# PLCBOARD.net
KiCad netlist of a schematic drawn in Altium Designer
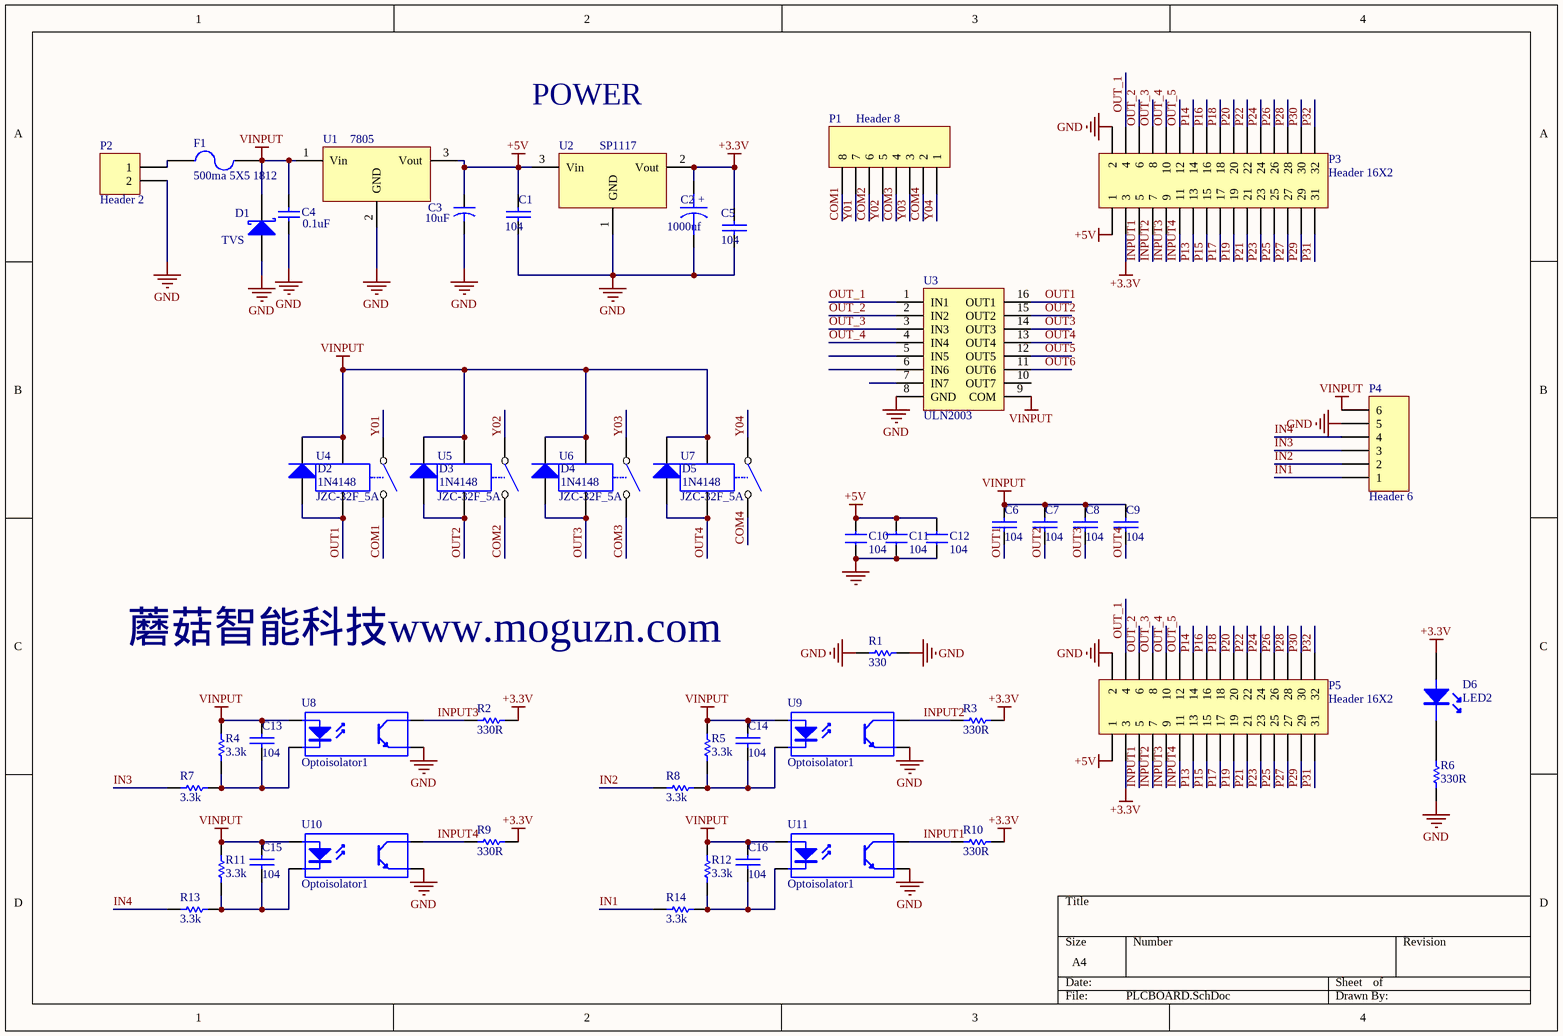
[diagram p0: PLCBOARD.SchDoc]

(export (version "E")
  (design (tool "Eeschema 10.0.6"))
  (components
    (comp (ref "C1")
      (value "104")
      (footprint "0805C1")
      (description "Capacitor")
      (libsource (lib "*") (part "CAP"))
    )
    (comp (ref "C2")
      (value "1000uf")
      (footprint "c6.3*5.3")
      (description "Capacitor")
      (libsource (lib "*") (part "CAPACITOR POL"))
    )
    (comp (ref "C3")
      (value "10uF")
      (footprint "RB.2/.4")
      (description "Capacitor")
      (fields (field (name "Comment") "Cap2") (field (name "PUBLISHER") "Altium Limited"))
      (libsource (lib "Miscellaneous Devices") (part "Cap2"))
    )
    (comp (ref "C4")
      (value "0.1uF")
      (footprint "0805C1")
      (description "Capacitor")
      (fields (field (name "Comment") "Cap") (field (name "PUBLISHER") "Altium Limited"))
      (libsource (lib "Miscellaneous Devices") (part "Cap"))
    )
    (comp (ref "C5")
      (value "104")
      (footprint "0805C1")
      (description "Capacitor")
      (libsource (lib "*") (part "CAP"))
    )
    (comp (ref "C6")
      (value "104")
      (footprint "0805C1")
      (description "Capacitor")
      (libsource (lib "*") (part "CAP"))
    )
    (comp (ref "C7")
      (value "104")
      (footprint "0805C1")
      (description "Capacitor")
      (libsource (lib "*") (part "CAP"))
    )
    (comp (ref "C8")
      (value "104")
      (footprint "0805C1")
      (description "Capacitor")
      (libsource (lib "*") (part "CAP"))
    )
    (comp (ref "C9")
      (value "104")
      (footprint "0805C1")
      (description "Capacitor")
      (libsource (lib "*") (part "CAP"))
    )
    (comp (ref "C10")
      (value "104")
      (footprint "0805C1")
      (description "Capacitor")
      (libsource (lib "") (part "CAP_1"))
    )
    (comp (ref "C11")
      (value "104")
      (footprint "0805C1")
      (description "Capacitor")
      (libsource (lib "") (part "CAP_1"))
    )
    (comp (ref "C12")
      (value "104")
      (footprint "0805C1")
      (description "Capacitor")
      (libsource (lib "") (part "CAP_1"))
    )
    (comp (ref "C13")
      (value "104")
      (footprint "0805C1")
      (description "Capacitor")
      (libsource (lib "*") (part "CAP"))
    )
    (comp (ref "C14")
      (value "104")
      (footprint "0805C1")
      (description "Capacitor")
      (libsource (lib "*") (part "CAP"))
    )
    (comp (ref "C15")
      (value "104")
      (footprint "0805C1")
      (description "Capacitor")
      (libsource (lib "*") (part "CAP"))
    )
    (comp (ref "C16")
      (value "104")
      (footprint "0805C1")
      (description "Capacitor")
      (libsource (lib "*") (part "CAP"))
    )
    (comp (ref "D1")
      (value "TVS")
      (footprint "do-214")
      (description "Schottky Diode")
      (fields (field (name "PUBLISHER") "Altium Limited"))
      (libsource (lib "Miscellaneous Devices") (part "D Schottky"))
    )
    (comp (ref "D2")
      (value "1N4148")
      (footprint "DIODE_SMD_4148")
      (description "Default Diode")
      (fields (field (name "PUBLISHER") "Altium Limited"))
      (libsource (lib "Miscellaneous Devices") (part "Diode"))
    )
    (comp (ref "D3")
      (value "1N4148")
      (footprint "DIODE_SMD_4148")
      (description "Default Diode")
      (fields (field (name "PUBLISHER") "Altium Limited"))
      (libsource (lib "Miscellaneous Devices") (part "Diode"))
    )
    (comp (ref "D4")
      (value "1N4148")
      (footprint "DIODE_SMD_4148")
      (description "Default Diode")
      (fields (field (name "PUBLISHER") "Altium Limited"))
      (libsource (lib "Miscellaneous Devices") (part "Diode"))
    )
    (comp (ref "D5")
      (value "1N4148")
      (footprint "DIODE_SMD_4148")
      (description "Default Diode")
      (fields (field (name "PUBLISHER") "Altium Limited"))
      (libsource (lib "Miscellaneous Devices") (part "Diode"))
    )
    (comp (ref "D6") (value "LED2") (footprint "0805LED") (libsource (lib "*") (part "LED")))
    (comp (ref "F1")
      (value "500ma 5X5 1812")
      (footprint "1812R")
      (description "Fuse")
      (fields (field (name "PUBLISHER") "Altium Limited"))
      (libsource (lib "Miscellaneous Devices") (part "Fuse 2"))
    )
    (comp (ref "P1")
      (value "Header 8")
      (footprint "CON8.6_8pin")
      (description "Header, 8-Pin")
      (fields (field (name "PUBLISHER") "Altium Limited"))
      (libsource (lib "Miscellaneous Connectors") (part "Header 8"))
    )
    (comp (ref "P2")
      (value "Header 2")
      (footprint "5VINPUT")
      (description "Header, 2-Pin")
      (fields (field (name "PUBLISHER") "Altium Limited"))
      (libsource (lib "Miscellaneous Connectors") (part "Header 2"))
    )
    (comp (ref "P3")
      (value "Header 16X2")
      (footprint "NDK2X16")
      (description "Header, 16-Pin, Dual row")
      (fields (field (name "PUBLISHER") "Altium Limited"))
      (libsource (lib "Miscellaneous Connectors") (part "Header 16X2"))
    )
    (comp (ref "P4")
      (value "Header 6")
      (footprint "CON7.62_6pin")
      (description "Header, 6-Pin")
      (fields (field (name "PUBLISHER") "Altium Limited"))
      (libsource (lib "Miscellaneous Connectors") (part "Header 6"))
    )
    (comp (ref "P5")
      (value "Header 16X2")
      (footprint "HDR2X16")
      (description "Header, 16-Pin, Dual row")
      (fields (field (name "PUBLISHER") "Altium Limited"))
      (libsource (lib "Miscellaneous Connectors") (part "Header 16X2"))
    )
    (comp (ref "R1")
      (value "330")
      (footprint "1812R")
      (description "Resistor")
      (fields (field (name "Comment") "Res1") (field (name "PUBLISHER") "Altium Limited"))
      (libsource (lib "Miscellaneous Devices") (part "Res1"))
    )
    (comp (ref "R2")
      (value "330R")
      (footprint "0805R1")
      (description "Resistor")
      (fields (field (name "Comment") "Res1") (field (name "PUBLISHER") "Altium Limited"))
      (libsource (lib "Miscellaneous Devices") (part "Res1"))
    )
    (comp (ref "R3")
      (value "330R")
      (footprint "0805R1")
      (description "Resistor")
      (fields (field (name "Comment") "Res1") (field (name "PUBLISHER") "Altium Limited"))
      (libsource (lib "Miscellaneous Devices") (part "Res1"))
    )
    (comp (ref "R4")
      (value "3.3k")
      (footprint "0805R1")
      (description "Resistor")
      (fields (field (name "Comment") "Res1") (field (name "PUBLISHER") "Altium Limited"))
      (libsource (lib "Miscellaneous Devices") (part "Res1"))
    )
    (comp (ref "R5")
      (value "3.3k")
      (footprint "0805R1")
      (description "Resistor")
      (fields (field (name "Comment") "Res1") (field (name "PUBLISHER") "Altium Limited"))
      (libsource (lib "Miscellaneous Devices") (part "Res1"))
    )
    (comp (ref "R6")
      (value "330R")
      (footprint "0805R1")
      (description "Resistor")
      (fields (field (name "Comment") "Res1") (field (name "PUBLISHER") "Altium Limited"))
      (libsource (lib "Miscellaneous Devices") (part "Res1"))
    )
    (comp (ref "R7")
      (value "3.3k")
      (footprint "0805R1")
      (description "Resistor")
      (fields (field (name "Comment") "Res1") (field (name "PUBLISHER") "Altium Limited"))
      (libsource (lib "Miscellaneous Devices") (part "Res1"))
    )
    (comp (ref "R8")
      (value "3.3k")
      (footprint "0805R1")
      (description "Resistor")
      (fields (field (name "Comment") "Res1") (field (name "PUBLISHER") "Altium Limited"))
      (libsource (lib "Miscellaneous Devices") (part "Res1"))
    )
    (comp (ref "R9")
      (value "330R")
      (footprint "0805R1")
      (description "Resistor")
      (fields (field (name "Comment") "Res1") (field (name "PUBLISHER") "Altium Limited"))
      (libsource (lib "Miscellaneous Devices") (part "Res1"))
    )
    (comp (ref "R10")
      (value "330R")
      (footprint "0805R1")
      (description "Resistor")
      (fields (field (name "Comment") "Res1") (field (name "PUBLISHER") "Altium Limited"))
      (libsource (lib "Miscellaneous Devices") (part "Res1"))
    )
    (comp (ref "R11")
      (value "3.3k")
      (footprint "0805R1")
      (description "Resistor")
      (fields (field (name "Comment") "Res1") (field (name "PUBLISHER") "Altium Limited"))
      (libsource (lib "Miscellaneous Devices") (part "Res1"))
    )
    (comp (ref "R12")
      (value "3.3k")
      (footprint "0805R1")
      (description "Resistor")
      (fields (field (name "Comment") "Res1") (field (name "PUBLISHER") "Altium Limited"))
      (libsource (lib "Miscellaneous Devices") (part "Res1"))
    )
    (comp (ref "R13")
      (value "3.3k")
      (footprint "0805R1")
      (description "Resistor")
      (fields (field (name "Comment") "Res1") (field (name "PUBLISHER") "Altium Limited"))
      (libsource (lib "Miscellaneous Devices") (part "Res1"))
    )
    (comp (ref "R14")
      (value "3.3k")
      (footprint "0805R1")
      (description "Resistor")
      (fields (field (name "Comment") "Res1") (field (name "PUBLISHER") "Altium Limited"))
      (libsource (lib "Miscellaneous Devices") (part "Res1"))
    )
    (comp (ref "U1") (value "7805") (footprint "7805") (libsource (lib "*") (part "7800")))
    (comp (ref "U2") (value "SP1117") (footprint "SOT-223") (libsource (lib "hhregulator") (part "SP1117")))
    (comp (ref "U3") (value "ULN2003") (footprint "SO-16") (libsource (lib "hhic") (part "ULN2003")))
    (comp (ref "U4")
      (value "JZC-32F_5A")
      (footprint "JZC-32F_5A")
      (libsource (lib "hhrelay") (part "JZC-32F_5A"))
    )
    (comp (ref "U5")
      (value "JZC-32F_5A")
      (footprint "JZC-32F_5A")
      (libsource (lib "hhrelay") (part "JZC-32F_5A"))
    )
    (comp (ref "U6")
      (value "JZC-32F_5A")
      (footprint "JZC-32F_5A")
      (libsource (lib "hhrelay") (part "JZC-32F_5A"))
    )
    (comp (ref "U7")
      (value "JZC-32F_5A")
      (footprint "NT90RHAE12CB_30A")
      (libsource (lib "hhrelay") (part "JZC-32F_5A"))
    )
    (comp (ref "U8")
      (value "Optoisolator1")
      (footprint "TLP181-2")
      (description "4-Pin Phototransistor Optocoupler")
      (fields (field (name "PUBLISHER") "Altium Limited"))
      (libsource (lib "Miscellaneous Devices") (part "Optoisolator1"))
    )
    (comp (ref "U9")
      (value "Optoisolator1")
      (footprint "TLP181-2")
      (description "4-Pin Phototransistor Optocoupler")
      (fields (field (name "PUBLISHER") "Altium Limited"))
      (libsource (lib "Miscellaneous Devices") (part "Optoisolator1"))
    )
    (comp (ref "U10")
      (value "Optoisolator1")
      (footprint "TLP181-2")
      (description "4-Pin Phototransistor Optocoupler")
      (fields (field (name "PUBLISHER") "Altium Limited"))
      (libsource (lib "Miscellaneous Devices") (part "Optoisolator1"))
    )
    (comp (ref "U11")
      (value "Optoisolator1")
      (footprint "TLP181-2")
      (description "4-Pin Phototransistor Optocoupler")
      (fields (field (name "PUBLISHER") "Altium Limited"))
      (libsource (lib "Miscellaneous Devices") (part "Optoisolator1"))
    )
  )
  (nets
    (net (code "1") (name "+3.3V") (class "Default")
      (node (ref "C2") (pin "1") (pinfunction "1_1") (pintype "passive"))
      (node (ref "C5") (pin "1") (pinfunction "1_1") (pintype "passive"))
      (node (ref "D6") (pin "1") (pinfunction "1_1") (pintype "passive"))
      (node (ref "P3") (pin "3") (pinfunction "3_3") (pintype "passive"))
      (node (ref "P5") (pin "3") (pinfunction "3_3") (pintype "passive"))
      (node (ref "R10") (pin "1") (pinfunction "1_1") (pintype "passive"))
      (node (ref "R2") (pin "1") (pinfunction "1_1") (pintype "passive"))
      (node (ref "R3") (pin "1") (pinfunction "1_1") (pintype "passive"))
      (node (ref "R9") (pin "1") (pinfunction "1_1") (pintype "passive"))
      (node (ref "U2") (pin "2") (pinfunction "Vout_2") (pintype "passive"))
    )
    (net (code "2") (name "+5V") (class "Default")
      (node (ref "C1") (pin "1") (pinfunction "1_1") (pintype "passive"))
      (node (ref "C10") (pin "2") (pinfunction "2_2") (pintype "passive"))
      (node (ref "C11") (pin "2") (pinfunction "2_2") (pintype "passive"))
      (node (ref "C12") (pin "2") (pinfunction "2_2") (pintype "passive"))
      (node (ref "C3") (pin "1") (pinfunction "1_1") (pintype "passive"))
      (node (ref "P3") (pin "1") (pinfunction "1_1") (pintype "passive"))
      (node (ref "P5") (pin "1") (pinfunction "1_1") (pintype "passive"))
      (node (ref "U1") (pin "3") (pinfunction "Vout_3") (pintype "passive"))
      (node (ref "U2") (pin "3") (pinfunction "Vin_3") (pintype "passive"))
    )
    (net (code "3") (name "/COM1") (class "Default")
      (node (ref "P1") (pin "8") (pinfunction "8_8") (pintype "passive"))
      (node (ref "U4") (pin "2") (pinfunction "2_2") (pintype "passive"))
    )
    (net (code "4") (name "/COM2") (class "Default")
      (node (ref "P1") (pin "6") (pinfunction "6_6") (pintype "passive"))
      (node (ref "U5") (pin "2") (pinfunction "2_2") (pintype "passive"))
    )
    (net (code "5") (name "/COM3") (class "Default")
      (node (ref "P1") (pin "4") (pinfunction "4_4") (pintype "passive"))
      (node (ref "U6") (pin "2") (pinfunction "2_2") (pintype "passive"))
    )
    (net (code "6") (name "/COM4") (class "Default")
      (node (ref "P1") (pin "2") (pinfunction "2_2") (pintype "passive"))
      (node (ref "U7") (pin "2") (pinfunction "2_2") (pintype "passive"))
    )
    (net (code "7") (name "/IN1") (class "Default")
      (node (ref "P4") (pin "1") (pinfunction "1_1") (pintype "passive"))
      (node (ref "R14") (pin "1") (pinfunction "1_1") (pintype "passive"))
    )
    (net (code "8") (name "/IN2") (class "Default")
      (node (ref "P4") (pin "2") (pinfunction "2_2") (pintype "passive"))
      (node (ref "R8") (pin "1") (pinfunction "1_1") (pintype "passive"))
    )
    (net (code "9") (name "/IN3") (class "Default")
      (node (ref "P4") (pin "3") (pinfunction "3_3") (pintype "passive"))
      (node (ref "R7") (pin "1") (pinfunction "1_1") (pintype "passive"))
    )
    (net (code "10") (name "/IN4") (class "Default")
      (node (ref "P4") (pin "4") (pinfunction "4_4") (pintype "passive"))
      (node (ref "R13") (pin "1") (pinfunction "1_1") (pintype "passive"))
    )
    (net (code "11") (name "/INPUT1") (class "Default")
      (node (ref "P3") (pin "5") (pinfunction "5_5") (pintype "passive"))
      (node (ref "P5") (pin "5") (pinfunction "5_5") (pintype "passive"))
      (node (ref "R10") (pin "2") (pinfunction "2_2") (pintype "passive"))
      (node (ref "U11") (pin "4") (pinfunction "C_4") (pintype "passive"))
    )
    (net (code "12") (name "/INPUT2") (class "Default")
      (node (ref "P3") (pin "7") (pinfunction "7_7") (pintype "passive"))
      (node (ref "P5") (pin "7") (pinfunction "7_7") (pintype "passive"))
      (node (ref "R3") (pin "2") (pinfunction "2_2") (pintype "passive"))
      (node (ref "U9") (pin "4") (pinfunction "C_4") (pintype "passive"))
    )
    (net (code "13") (name "/INPUT3") (class "Default")
      (node (ref "P3") (pin "9") (pinfunction "9_9") (pintype "passive"))
      (node (ref "P5") (pin "9") (pinfunction "9_9") (pintype "passive"))
      (node (ref "R2") (pin "2") (pinfunction "2_2") (pintype "passive"))
      (node (ref "U8") (pin "4") (pinfunction "C_4") (pintype "passive"))
    )
    (net (code "14") (name "/INPUT4") (class "Default")
      (node (ref "P3") (pin "11") (pinfunction "11_11") (pintype "passive"))
      (node (ref "P5") (pin "11") (pinfunction "11_11") (pintype "passive"))
      (node (ref "R9") (pin "2") (pinfunction "2_2") (pintype "passive"))
      (node (ref "U10") (pin "4") (pinfunction "C_4") (pintype "passive"))
    )
    (net (code "15") (name "/OUT1") (class "Default")
      (node (ref "C6") (pin "2") (pinfunction "2_2") (pintype "passive"))
      (node (ref "D2") (pin "1") (pinfunction "A_1") (pintype "passive"))
      (node (ref "U3") (pin "16") (pinfunction "OUT1_16") (pintype "passive"))
      (node (ref "U4") (pin "4") (pinfunction "4_4") (pintype "passive"))
    )
    (net (code "16") (name "/OUT2") (class "Default")
      (node (ref "C7") (pin "2") (pinfunction "2_2") (pintype "passive"))
      (node (ref "D3") (pin "1") (pinfunction "A_1") (pintype "passive"))
      (node (ref "U3") (pin "15") (pinfunction "OUT2_15") (pintype "passive"))
      (node (ref "U5") (pin "4") (pinfunction "4_4") (pintype "passive"))
    )
    (net (code "17") (name "/OUT3") (class "Default")
      (node (ref "C8") (pin "2") (pinfunction "2_2") (pintype "passive"))
      (node (ref "D4") (pin "1") (pinfunction "A_1") (pintype "passive"))
      (node (ref "U3") (pin "14") (pinfunction "OUT3_14") (pintype "passive"))
      (node (ref "U6") (pin "4") (pinfunction "4_4") (pintype "passive"))
    )
    (net (code "18") (name "/OUT4") (class "Default")
      (node (ref "C9") (pin "2") (pinfunction "2_2") (pintype "passive"))
      (node (ref "D5") (pin "1") (pinfunction "A_1") (pintype "passive"))
      (node (ref "U3") (pin "13") (pinfunction "OUT4_13") (pintype "passive"))
      (node (ref "U7") (pin "4") (pinfunction "4_4") (pintype "passive"))
    )
    (net (code "19") (name "/OUT5") (class "Default")
      (node (ref "U3") (pin "12") (pinfunction "OUT5_12") (pintype "passive"))
    )
    (net (code "20") (name "/OUT6") (class "Default")
      (node (ref "U3") (pin "11") (pinfunction "OUT6_11") (pintype "passive"))
    )
    (net (code "21") (name "/OUT_1") (class "Default")
      (node (ref "P3") (pin "4") (pinfunction "4_4") (pintype "passive"))
      (node (ref "P5") (pin "4") (pinfunction "4_4") (pintype "passive"))
      (node (ref "U3") (pin "1") (pinfunction "IN1_1") (pintype "passive"))
    )
    (net (code "22") (name "/OUT_2") (class "Default")
      (node (ref "P3") (pin "6") (pinfunction "6_6") (pintype "passive"))
      (node (ref "P5") (pin "6") (pinfunction "6_6") (pintype "passive"))
      (node (ref "U3") (pin "2") (pinfunction "IN2_2") (pintype "passive"))
    )
    (net (code "23") (name "/OUT_3") (class "Default")
      (node (ref "P3") (pin "8") (pinfunction "8_8") (pintype "passive"))
      (node (ref "P5") (pin "8") (pinfunction "8_8") (pintype "passive"))
      (node (ref "U3") (pin "3") (pinfunction "IN3_3") (pintype "passive"))
    )
    (net (code "24") (name "/OUT_4") (class "Default")
      (node (ref "P3") (pin "10") (pinfunction "10_10") (pintype "passive"))
      (node (ref "P5") (pin "10") (pinfunction "10_10") (pintype "passive"))
      (node (ref "U3") (pin "4") (pinfunction "IN4_4") (pintype "passive"))
    )
    (net (code "25") (name "/OUT_5") (class "Default")
      (node (ref "P3") (pin "12") (pinfunction "12_12") (pintype "passive"))
      (node (ref "P5") (pin "12") (pinfunction "12_12") (pintype "passive"))
    )
    (net (code "26") (name "/P13") (class "Default")
      (node (ref "P3") (pin "13") (pinfunction "13_13") (pintype "passive"))
      (node (ref "P5") (pin "13") (pinfunction "13_13") (pintype "passive"))
    )
    (net (code "27") (name "/P14") (class "Default")
      (node (ref "P3") (pin "14") (pinfunction "14_14") (pintype "passive"))
      (node (ref "P5") (pin "14") (pinfunction "14_14") (pintype "passive"))
    )
    (net (code "28") (name "/P15") (class "Default")
      (node (ref "P3") (pin "15") (pinfunction "15_15") (pintype "passive"))
      (node (ref "P5") (pin "15") (pinfunction "15_15") (pintype "passive"))
    )
    (net (code "29") (name "/P16") (class "Default")
      (node (ref "P3") (pin "16") (pinfunction "16_16") (pintype "passive"))
      (node (ref "P5") (pin "16") (pinfunction "16_16") (pintype "passive"))
    )
    (net (code "30") (name "/P17") (class "Default")
      (node (ref "P3") (pin "17") (pinfunction "17_17") (pintype "passive"))
      (node (ref "P5") (pin "17") (pinfunction "17_17") (pintype "passive"))
    )
    (net (code "31") (name "/P18") (class "Default")
      (node (ref "P3") (pin "18") (pinfunction "18_18") (pintype "passive"))
      (node (ref "P5") (pin "18") (pinfunction "18_18") (pintype "passive"))
    )
    (net (code "32") (name "/P19") (class "Default")
      (node (ref "P3") (pin "19") (pinfunction "19_19") (pintype "passive"))
      (node (ref "P5") (pin "19") (pinfunction "19_19") (pintype "passive"))
    )
    (net (code "33") (name "/P20") (class "Default")
      (node (ref "P3") (pin "20") (pinfunction "20_20") (pintype "passive"))
      (node (ref "P5") (pin "20") (pinfunction "20_20") (pintype "passive"))
    )
    (net (code "34") (name "/P21") (class "Default")
      (node (ref "P3") (pin "21") (pinfunction "21_21") (pintype "passive"))
      (node (ref "P5") (pin "21") (pinfunction "21_21") (pintype "passive"))
    )
    (net (code "35") (name "/P22") (class "Default")
      (node (ref "P3") (pin "22") (pinfunction "22_22") (pintype "passive"))
      (node (ref "P5") (pin "22") (pinfunction "22_22") (pintype "passive"))
    )
    (net (code "36") (name "/P23") (class "Default")
      (node (ref "P3") (pin "23") (pinfunction "23_23") (pintype "passive"))
      (node (ref "P5") (pin "23") (pinfunction "23_23") (pintype "passive"))
    )
    (net (code "37") (name "/P24") (class "Default")
      (node (ref "P3") (pin "24") (pinfunction "24_24") (pintype "passive"))
      (node (ref "P5") (pin "24") (pinfunction "24_24") (pintype "passive"))
    )
    (net (code "38") (name "/P25") (class "Default")
      (node (ref "P3") (pin "25") (pinfunction "25_25") (pintype "passive"))
      (node (ref "P5") (pin "25") (pinfunction "25_25") (pintype "passive"))
    )
    (net (code "39") (name "/P26") (class "Default")
      (node (ref "P3") (pin "26") (pinfunction "26_26") (pintype "passive"))
      (node (ref "P5") (pin "26") (pinfunction "26_26") (pintype "passive"))
    )
    (net (code "40") (name "/P27") (class "Default")
      (node (ref "P3") (pin "27") (pinfunction "27_27") (pintype "passive"))
      (node (ref "P5") (pin "27") (pinfunction "27_27") (pintype "passive"))
    )
    (net (code "41") (name "/P28") (class "Default")
      (node (ref "P3") (pin "28") (pinfunction "28_28") (pintype "passive"))
      (node (ref "P5") (pin "28") (pinfunction "28_28") (pintype "passive"))
    )
    (net (code "42") (name "/P29") (class "Default")
      (node (ref "P3") (pin "29") (pinfunction "29_29") (pintype "passive"))
      (node (ref "P5") (pin "29") (pinfunction "29_29") (pintype "passive"))
    )
    (net (code "43") (name "/P30") (class "Default")
      (node (ref "P3") (pin "30") (pinfunction "30_30") (pintype "passive"))
      (node (ref "P5") (pin "30") (pinfunction "30_30") (pintype "passive"))
    )
    (net (code "44") (name "/P31") (class "Default")
      (node (ref "P3") (pin "31") (pinfunction "31_31") (pintype "passive"))
      (node (ref "P5") (pin "31") (pinfunction "31_31") (pintype "passive"))
    )
    (net (code "45") (name "/P32") (class "Default")
      (node (ref "P3") (pin "32") (pinfunction "32_32") (pintype "passive"))
      (node (ref "P5") (pin "32") (pinfunction "32_32") (pintype "passive"))
    )
    (net (code "46") (name "/Y01") (class "Default")
      (node (ref "P1") (pin "7") (pinfunction "7_7") (pintype "passive"))
      (node (ref "U4") (pin "1") (pinfunction "1_1") (pintype "passive"))
    )
    (net (code "47") (name "/Y02") (class "Default")
      (node (ref "P1") (pin "5") (pinfunction "5_5") (pintype "passive"))
      (node (ref "U5") (pin "1") (pinfunction "1_1") (pintype "passive"))
    )
    (net (code "48") (name "/Y03") (class "Default")
      (node (ref "P1") (pin "3") (pinfunction "3_3") (pintype "passive"))
      (node (ref "U6") (pin "1") (pinfunction "1_1") (pintype "passive"))
    )
    (net (code "49") (name "/Y04") (class "Default")
      (node (ref "P1") (pin "1") (pinfunction "1_1") (pintype "passive"))
      (node (ref "U7") (pin "1") (pinfunction "1_1") (pintype "passive"))
    )
    (net (code "50") (name "GND") (class "Default")
      (node (ref "C1") (pin "2") (pinfunction "2_2") (pintype "passive"))
      (node (ref "C10") (pin "1") (pinfunction "1_1") (pintype "passive"))
      (node (ref "C11") (pin "1") (pinfunction "1_1") (pintype "passive"))
      (node (ref "C12") (pin "1") (pinfunction "1_1") (pintype "passive"))
      (node (ref "C2") (pin "2") (pinfunction "2_2") (pintype "passive"))
      (node (ref "C3") (pin "2") (pinfunction "2_2") (pintype "passive"))
      (node (ref "C4") (pin "1") (pinfunction "1_1") (pintype "passive"))
      (node (ref "C5") (pin "2") (pinfunction "2_2") (pintype "passive"))
      (node (ref "D1") (pin "1") (pinfunction "A_1") (pintype "passive"))
      (node (ref "P2") (pin "2") (pinfunction "2_2") (pintype "passive"))
      (node (ref "P3") (pin "2") (pinfunction "2_2") (pintype "passive"))
      (node (ref "P4") (pin "5") (pinfunction "5_5") (pintype "passive"))
      (node (ref "P5") (pin "2") (pinfunction "2_2") (pintype "passive"))
      (node (ref "R1") (pin "1") (pinfunction "1_1") (pintype "passive"))
      (node (ref "R1") (pin "2") (pinfunction "2_2") (pintype "passive"))
      (node (ref "R6") (pin "2") (pinfunction "2_2") (pintype "passive"))
      (node (ref "U1") (pin "2") (pinfunction "GND_2") (pintype "passive"))
      (node (ref "U10") (pin "3") (pinfunction "E_3") (pintype "passive"))
      (node (ref "U11") (pin "3") (pinfunction "E_3") (pintype "passive"))
      (node (ref "U2") (pin "1") (pinfunction "GND_1") (pintype "passive"))
      (node (ref "U3") (pin "8") (pinfunction "GND_8") (pintype "passive"))
      (node (ref "U8") (pin "3") (pinfunction "E_3") (pintype "passive"))
      (node (ref "U9") (pin "3") (pinfunction "E_3") (pintype "passive"))
    )
    (net (code "51") (name "Net-(D6-Pad2)") (class "Default")
      (node (ref "D6") (pin "2") (pinfunction "2_2") (pintype "passive"))
      (node (ref "R6") (pin "1") (pinfunction "1_1") (pintype "passive"))
    )
    (net (code "52") (name "Net-(F1-Pad1)") (class "Default")
      (node (ref "F1") (pin "1") (pinfunction "1_1") (pintype "passive"))
      (node (ref "P2") (pin "1") (pinfunction "1_1") (pintype "passive"))
    )
    (net (code "53") (name "Net-(U8-K)") (class "Default")
      (node (ref "C13") (pin "2") (pinfunction "2_2") (pintype "passive"))
      (node (ref "R4") (pin "2") (pinfunction "2_2") (pintype "passive"))
      (node (ref "R7") (pin "2") (pinfunction "2_2") (pintype "passive"))
      (node (ref "U8") (pin "2") (pinfunction "K_2") (pintype "passive"))
    )
    (net (code "54") (name "Net-(U9-K)") (class "Default")
      (node (ref "C14") (pin "2") (pinfunction "2_2") (pintype "passive"))
      (node (ref "R5") (pin "2") (pinfunction "2_2") (pintype "passive"))
      (node (ref "R8") (pin "2") (pinfunction "2_2") (pintype "passive"))
      (node (ref "U9") (pin "2") (pinfunction "K_2") (pintype "passive"))
    )
    (net (code "55") (name "Net-(U10-K)") (class "Default")
      (node (ref "C15") (pin "2") (pinfunction "2_2") (pintype "passive"))
      (node (ref "R11") (pin "2") (pinfunction "2_2") (pintype "passive"))
      (node (ref "R13") (pin "2") (pinfunction "2_2") (pintype "passive"))
      (node (ref "U10") (pin "2") (pinfunction "K_2") (pintype "passive"))
    )
    (net (code "56") (name "Net-(U11-K)") (class "Default")
      (node (ref "C16") (pin "2") (pinfunction "2_2") (pintype "passive"))
      (node (ref "R12") (pin "2") (pinfunction "2_2") (pintype "passive"))
      (node (ref "R14") (pin "2") (pinfunction "2_2") (pintype "passive"))
      (node (ref "U11") (pin "2") (pinfunction "K_2") (pintype "passive"))
    )
    (net (code "57") (name "VINPUT") (class "Default")
      (node (ref "C13") (pin "1") (pinfunction "1_1") (pintype "passive"))
      (node (ref "C14") (pin "1") (pinfunction "1_1") (pintype "passive"))
      (node (ref "C15") (pin "1") (pinfunction "1_1") (pintype "passive"))
      (node (ref "C16") (pin "1") (pinfunction "1_1") (pintype "passive"))
      (node (ref "C4") (pin "2") (pinfunction "2_2") (pintype "passive"))
      (node (ref "C6") (pin "1") (pinfunction "1_1") (pintype "passive"))
      (node (ref "C7") (pin "1") (pinfunction "1_1") (pintype "passive"))
      (node (ref "C8") (pin "1") (pinfunction "1_1") (pintype "passive"))
      (node (ref "C9") (pin "1") (pinfunction "1_1") (pintype "passive"))
      (node (ref "D1") (pin "2") (pinfunction "K_2") (pintype "passive"))
      (node (ref "D2") (pin "2") (pinfunction "K_2") (pintype "passive"))
      (node (ref "D3") (pin "2") (pinfunction "K_2") (pintype "passive"))
      (node (ref "D4") (pin "2") (pinfunction "K_2") (pintype "passive"))
      (node (ref "D5") (pin "2") (pinfunction "K_2") (pintype "passive"))
      (node (ref "F1") (pin "2") (pinfunction "2_2") (pintype "passive"))
      (node (ref "P4") (pin "6") (pinfunction "6_6") (pintype "passive"))
      (node (ref "R11") (pin "1") (pinfunction "1_1") (pintype "passive"))
      (node (ref "R12") (pin "1") (pinfunction "1_1") (pintype "passive"))
      (node (ref "R4") (pin "1") (pinfunction "1_1") (pintype "passive"))
      (node (ref "R5") (pin "1") (pinfunction "1_1") (pintype "passive"))
      (node (ref "U1") (pin "1") (pinfunction "Vin_1") (pintype "passive"))
      (node (ref "U10") (pin "1") (pinfunction "A_1") (pintype "passive"))
      (node (ref "U11") (pin "1") (pinfunction "A_1") (pintype "passive"))
      (node (ref "U3") (pin "9") (pinfunction "COM_9") (pintype "passive"))
      (node (ref "U4") (pin "3") (pinfunction "3_3") (pintype "passive"))
      (node (ref "U5") (pin "3") (pinfunction "3_3") (pintype "passive"))
      (node (ref "U6") (pin "3") (pinfunction "3_3") (pintype "passive"))
      (node (ref "U7") (pin "3") (pinfunction "3_3") (pintype "passive"))
      (node (ref "U8") (pin "1") (pinfunction "A_1") (pintype "passive"))
      (node (ref "U9") (pin "1") (pinfunction "A_1") (pintype "passive"))
    )
    (net (code "58") (name "unconnected-(U3-IN5-Pad5)") (class "Default")
      (node (ref "U3") (pin "5") (pinfunction "IN5_5") (pintype "passive"))
    )
    (net (code "59") (name "unconnected-(U3-IN6-Pad6)") (class "Default")
      (node (ref "U3") (pin "6") (pinfunction "IN6_6") (pintype "passive"))
    )
    (net (code "60") (name "unconnected-(U3-IN7-Pad7)") (class "Default")
      (node (ref "U3") (pin "7") (pinfunction "IN7_7") (pintype "passive"))
    )
    (net (code "61") (name "unconnected-(U3-OUT7-Pad10)") (class "Default")
      (node (ref "U3") (pin "10") (pinfunction "OUT7_10") (pintype "passive"))
    )
  )
)
